# Power_3V3.net
KiCad netlist of a schematic drawn in Altium Designer
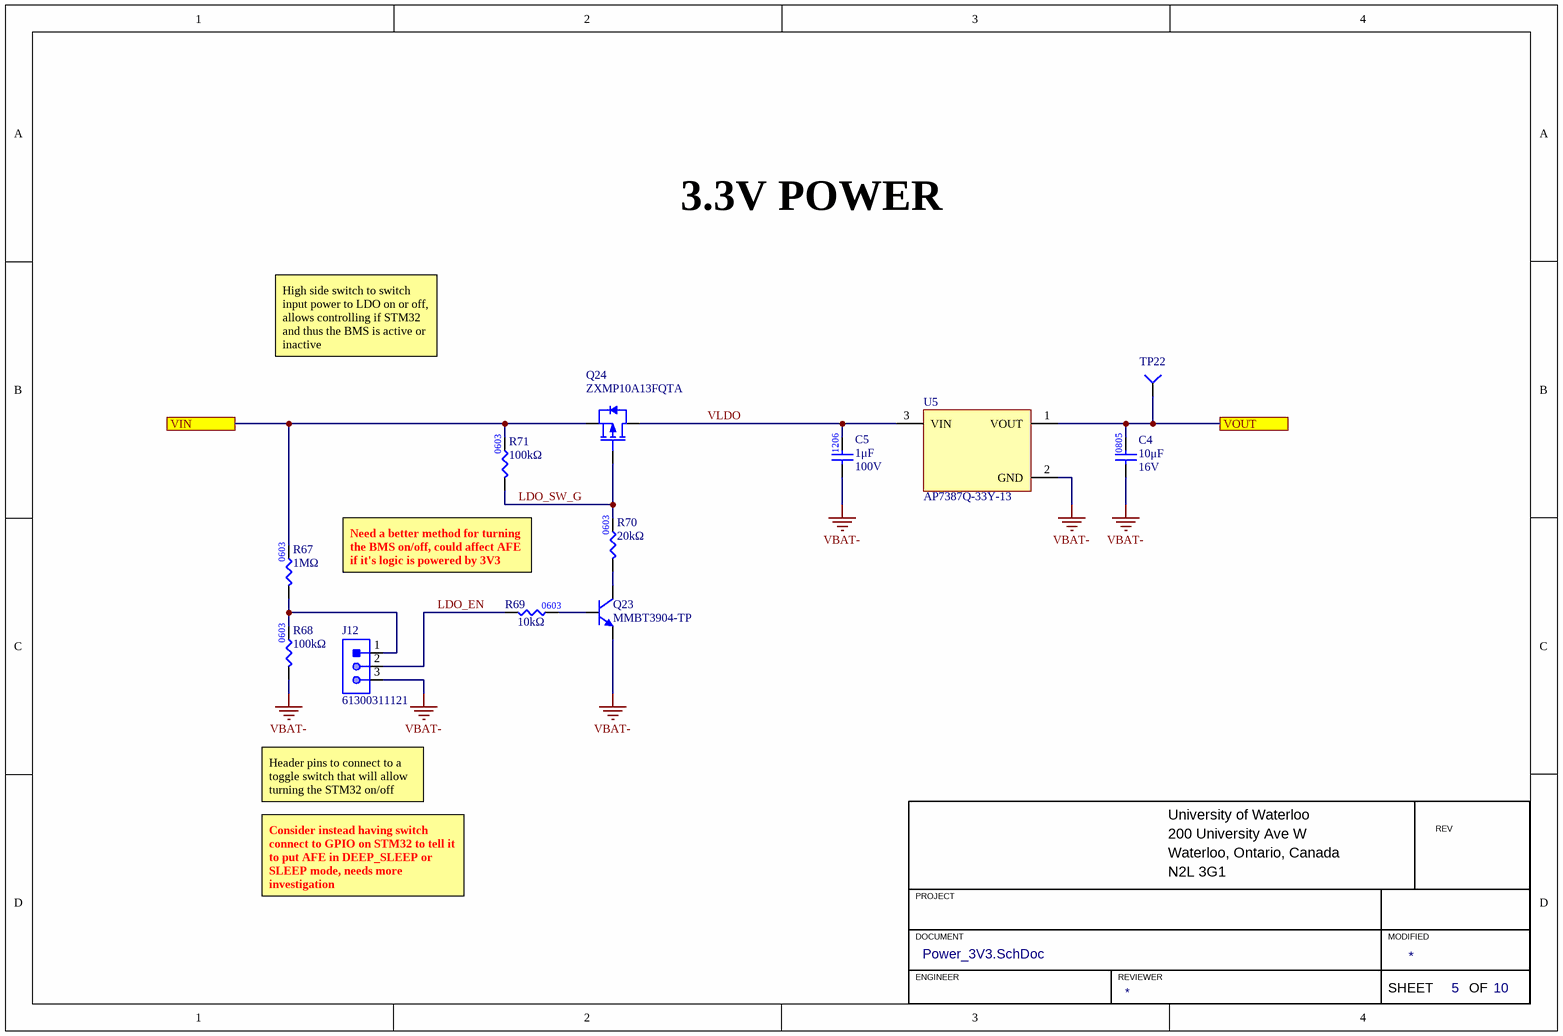
[diagram p0: Power_3V3.SchDoc]

(export (version "E")
  (design (tool "Eeschema 10.0.6"))
  (components
    (comp (ref "C4")
      (value "10μF")
      (footprint "CAP2012")
      (description "CAP CER 10UF 16V X5R 0805")
      (fields (field (name "VOLTAGE RATING") "16V") (field (name "Comment") "CAP_10uF_16V_0805"))
      (libsource (lib "Personal_Schematic_Library_2022") (part "CAP_10uF_16V_0805"))
    )
    (comp (ref "C5")
      (value "1μF")
      (footprint "CAPC3216X190X50NL20T25")
      (description "CAP CER 1UF 100V X7R 1206")
      (fields (field (name "VOLTAGE RATING") "100V") (field (name "Comment") "CAP_1uF_100V_1206"))
      (libsource (lib "Personal_Schematic_Library_2022") (part "CAP_1uF_100V_1206"))
    )
    (comp (ref "J12")
      (value "HEADER 3x1")
      (footprint "HDR1X3")
      (description "CONN HEADER VERT 3POS 2.54MM")
      (fields (field (name "MANUFACTURER PART NUMBER 1") "61300311121"))
      (libsource (lib "Personal_Schematic_Library_2022") (part "HEADER 3x1"))
    )
    (comp (ref "Q23")
      (value "NPN_40V_100mA")
      (footprint "SOT23-3")
      (description "TRANS NPN 40V 0.2A SOT23")
      (fields (field (name "MANUFACTURER PART NUMBER 1") "MMBT3904-TP"))
      (libsource (lib "Personal_Schematic_Library_2022") (part "NPN_40V_100mA"))
    )
    (comp (ref "Q24")
      (value "PMOS_100V_600mA")
      (footprint "SOT23-3")
      (description "MOSFET P-CH 100V 600MA SOT23")
      (fields (field (name "MANUFACTURER PART NUMBER 1") "ZXMP10A13FQTA"))
      (libsource (lib "Personal_Schematic_Library_2022") (part "PMOS_100V_600mA"))
    )
    (comp (ref "R67")
      (value "1MΩ")
      (footprint "RES0603")
      (description "RES 1M OHM 1% 1/10W 0603")
      (fields (field (name "Comment") "RES_1MΩ_0603_1%"))
      (libsource (lib "Personal_Schematic_Library_2022") (part "RES_1MΩ_0603_1%"))
    )
    (comp (ref "R68")
      (value "100kΩ")
      (footprint "RES0603")
      (description "RES 100K OHM 1% 1/10W 0603")
      (fields (field (name "Comment") "RES_100kΩ_0603_1%"))
      (libsource (lib "Personal_Schematic_Library_2022") (part "RES_100kΩ_0603_1%"))
    )
    (comp (ref "R69")
      (value "10kΩ")
      (footprint "RES0603")
      (description "RES 10K OHM 1% 1/8W 0603")
      (fields (field (name "Comment") "RES_10kΩ_0603_1%"))
      (libsource (lib "Personal_Schematic_Library_2022") (part "RES_10kΩ_0603_1%"))
    )
    (comp (ref "R70")
      (value "20kΩ")
      (footprint "RES0603")
      (description "RES 20K OHM 1% 1/10W 0603")
      (fields (field (name "Comment") "RES_20kΩ_0603_1%"))
      (libsource (lib "Personal_Schematic_Library_2022") (part "RES_20kΩ_0603_1%"))
    )
    (comp (ref "R71")
      (value "100kΩ")
      (footprint "RES0603")
      (description "RES 100K OHM 1% 1/10W 0603")
      (fields (field (name "Comment") "RES_100kΩ_0603_1%"))
      (libsource (lib "Personal_Schematic_Library_2022") (part "RES_100kΩ_0603_1%"))
    )
    (comp (ref "TP22")
      (value "TESTPOINT_SMD_LOOP")
      (footprint "S1751-46R")
      (description "TESTPOINT SMD LOOP")
      (libsource (lib "UWRT_Schematic_Library_2020") (part "TESTPOINT_SMD_LOOP"))
    )
    (comp (ref "U5")
      (value "LDO_3.3V_150mA_60VIN")
      (footprint "SOT89")
      (description "IC REG LINEAR 3.3V 150MA SOT89-3")
      (fields (field (name "MANUFACTURER PART NUMBER 1") "AP7387Q-33Y-13"))
      (libsource (lib "Personal_Schematic_Library_2022") (part "LDO_3.3V_150mA_60VIN"))
    )
  )
  (nets
    (net (code "1") (name "/LDO_EN") (class "Default")
      (node (ref "J12") (pin "2") (pinfunction "2_2") (pintype "passive"))
      (node (ref "R69") (pin "1") (pinfunction "1_1") (pintype "passive"))
    )
    (net (code "2") (name "/LDO_SW_G") (class "Default")
      (node (ref "Q24") (pin "1") (pinfunction "Gate_1") (pintype "passive"))
      (node (ref "R70") (pin "2") (pinfunction "2_2") (pintype "passive"))
      (node (ref "R71") (pin "1") (pinfunction "1_1") (pintype "passive"))
    )
    (net (code "3") (name "/VIN") (class "Default")
      (node (ref "Q24") (pin "2") (pinfunction "Source_2") (pintype "passive"))
      (node (ref "R67") (pin "2") (pinfunction "2_2") (pintype "passive"))
      (node (ref "R71") (pin "2") (pinfunction "2_2") (pintype "passive"))
    )
    (net (code "4") (name "/VLDO") (class "Default")
      (node (ref "C5") (pin "2") (pinfunction "2_2") (pintype "passive"))
      (node (ref "Q24") (pin "3") (pinfunction "Drain_3") (pintype "passive"))
      (node (ref "U5") (pin "3") (pinfunction "VIN_3") (pintype "power_in"))
    )
    (net (code "5") (name "/VOUT") (class "Default")
      (node (ref "C4") (pin "2") (pinfunction "2_2") (pintype "passive"))
      (node (ref "TP22") (pin "1") (pinfunction "=value_1") (pintype "passive"))
      (node (ref "U5") (pin "1") (pinfunction "VOUT_1") (pintype "power_in"))
    )
    (net (code "6") (name "Net-(J12-Pad1)") (class "Default")
      (node (ref "J12") (pin "1") (pinfunction "1_1") (pintype "passive"))
      (node (ref "R67") (pin "1") (pinfunction "1_1") (pintype "passive"))
      (node (ref "R68") (pin "2") (pinfunction "2_2") (pintype "passive"))
    )
    (net (code "7") (name "Net-(Q23-B)") (class "Default")
      (node (ref "Q23") (pin "1") (pinfunction "B_1") (pintype "passive"))
      (node (ref "R69") (pin "2") (pinfunction "2_2") (pintype "passive"))
    )
    (net (code "8") (name "Net-(Q23-C)") (class "Default")
      (node (ref "Q23") (pin "3") (pinfunction "C_3") (pintype "passive"))
      (node (ref "R70") (pin "1") (pinfunction "1_1") (pintype "passive"))
    )
    (net (code "9") (name "VBAT-") (class "Default")
      (node (ref "C4") (pin "1") (pinfunction "1_1") (pintype "passive"))
      (node (ref "C5") (pin "1") (pinfunction "1_1") (pintype "passive"))
      (node (ref "J12") (pin "3") (pinfunction "3_3") (pintype "passive"))
      (node (ref "Q23") (pin "2") (pinfunction "E_2") (pintype "passive"))
      (node (ref "R68") (pin "1") (pinfunction "1_1") (pintype "passive"))
      (node (ref "U5") (pin "2") (pinfunction "GND_2") (pintype "power_in"))
    )
  )
)
